# untitled.net
KiCad netlist of a schematic drawn in EAGLE
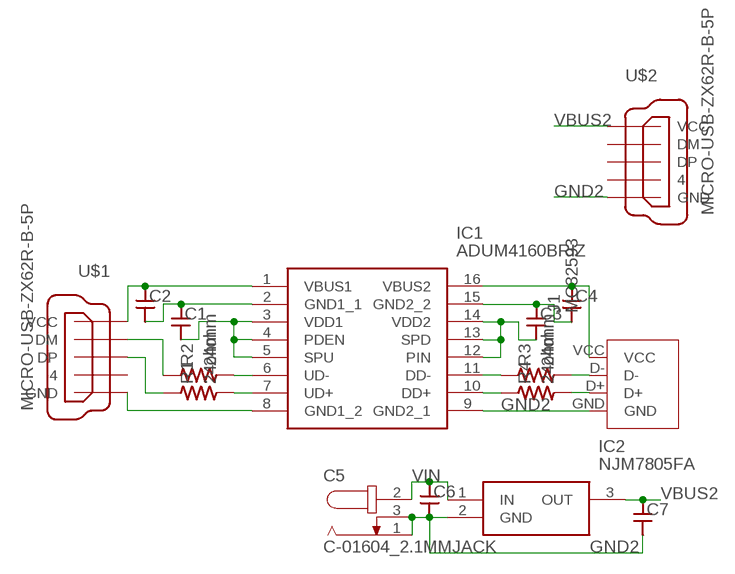
[diagram p0: schematic, sheet 1]

(export (version "E")
  (design (tool "Eeschema 10.0.6"))
  (components
    (comp (ref "C1")
      (value "CAPACITOR2012")
      (footprint "eagle-import:SMD2012")
      (libsource (lib "eagle-import") (part "CAPACITOR2012"))
    )
    (comp (ref "C2")
      (value "CAPACITOR2012")
      (footprint "eagle-import:SMD2012")
      (libsource (lib "eagle-import") (part "CAPACITOR2012"))
    )
    (comp (ref "C3")
      (value "CAPACITOR2012")
      (footprint "eagle-import:SMD2012")
      (libsource (lib "eagle-import") (part "CAPACITOR2012"))
    )
    (comp (ref "C4")
      (value "CAPACITOR2012")
      (footprint "eagle-import:SMD2012")
      (libsource (lib "eagle-import") (part "CAPACITOR2012"))
    )
    (comp (ref "C5")
      (value "C-01604_2.1MMJACK")
      (footprint "eagle-import:2.1MMJACK")
      (libsource (lib "eagle-import") (part "C-01604_2.1MMJACK"))
    )
    (comp (ref "C6")
      (value "CAPACITOR2012")
      (footprint "eagle-import:SMD2012")
      (libsource (lib "eagle-import") (part "CAPACITOR2012"))
    )
    (comp (ref "C7")
      (value "CAPACITOR2012")
      (footprint "eagle-import:SMD2012")
      (libsource (lib "eagle-import") (part "CAPACITOR2012"))
    )
    (comp (ref "IC1")
      (value "ADUM4160BRIZ")
      (footprint "eagle-import:SOIC127P1032X265-16N")
      (fields
        (field (name "MOUSER_PART_NUMBER") "584-ADUM4160BRIZ")
        (field (name "RS_PART_NUMBER") "9129894")
      )
      (libsource (lib "eagle-import") (part "ADUM4160BRIZ"))
    )
    (comp (ref "IC2")
      (value "NJM7805FA")
      (footprint "eagle-import:TO254P500X1000X2170-3P")
      (libsource (lib "eagle-import") (part "NJM7805FA"))
    )
    (comp (ref "J1")
      (value "MC32593")
      (footprint "eagle-import:MC32593")
      (libsource (lib "eagle-import") (part "MC32593"))
    )
    (comp (ref "R1")
      (value "24ohm")
      (footprint "eagle-import:SMD1608")
      (libsource (lib "eagle-import") (part "RESISTOR-US1608"))
    )
    (comp (ref "R2")
      (value "24ohm")
      (footprint "eagle-import:SMD1608")
      (libsource (lib "eagle-import") (part "RESISTOR-US1608"))
    )
    (comp (ref "R3")
      (value "24ohm")
      (footprint "eagle-import:SMD1608")
      (libsource (lib "eagle-import") (part "RESISTOR-US1608"))
    )
    (comp (ref "R4")
      (value "24ohm")
      (footprint "eagle-import:SMD1608")
      (libsource (lib "eagle-import") (part "RESISTOR-US1608"))
    )
    (comp (ref "U$1")
      (value "MICRO-USB-ZX62R-B-5P")
      (footprint "eagle-import:ZX62R-B-5P")
      (libsource (lib "eagle-import") (part "MICRO-USB-ZX62R-B-5P"))
    )
    (comp (ref "U$2")
      (value "MICRO-USB-ZX62R-B-5P")
      (footprint "eagle-import:ZX62R-B-5P")
      (libsource (lib "eagle-import") (part "MICRO-USB-ZX62R-B-5P"))
    )
  )
  (nets
    (net (code "1") (name "/GND1") (class "Default")
      (node (ref "C1") (pin "1") (pinfunction "1_1") (pintype "passive"))
      (node (ref "C2") (pin "2") (pinfunction "2_2") (pintype "passive"))
      (node (ref "IC1") (pin "2") (pinfunction "GND1_1_2") (pintype "bidirectional"))
      (node (ref "IC1") (pin "8") (pinfunction "GND1_2_8") (pintype "bidirectional"))
      (node (ref "U$1") (pin "5") (pinfunction "GND_5") (pintype "input"))
    )
    (net (code "2") (name "/GND2") (class "Default")
      (node (ref "C3") (pin "1") (pinfunction "1_1") (pintype "passive"))
      (node (ref "C4") (pin "2") (pinfunction "2_2") (pintype "passive"))
      (node (ref "C5") (pin "1") (pinfunction "GND_1") (pintype "passive"))
      (node (ref "C5") (pin "3") (pinfunction "S_3") (pintype "passive"))
      (node (ref "C6") (pin "2") (pinfunction "2_2") (pintype "passive"))
      (node (ref "C7") (pin "2") (pinfunction "2_2") (pintype "passive"))
      (node (ref "IC1") (pin "15") (pinfunction "GND2_2_15") (pintype "bidirectional"))
      (node (ref "IC1") (pin "9") (pinfunction "GND2_1_9") (pintype "bidirectional"))
      (node (ref "IC2") (pin "2") (pinfunction "GND_2") (pintype "power_in"))
      (node (ref "J1") (pin "GND") (pinfunction "GND_GND") (pintype "bidirectional"))
      (node (ref "U$2") (pin "5") (pinfunction "GND_5") (pintype "input"))
    )
    (net (code "3") (name "/VBUS2") (class "Default")
      (node (ref "C4") (pin "1") (pinfunction "1_1") (pintype "passive"))
      (node (ref "C7") (pin "1") (pinfunction "1_1") (pintype "passive"))
      (node (ref "IC1") (pin "16") (pinfunction "VBUS2_16") (pintype "bidirectional"))
      (node (ref "IC2") (pin "3") (pinfunction "OUT_3") (pintype "output"))
      (node (ref "J1") (pin "VCC") (pinfunction "VCC_VCC") (pintype "bidirectional"))
      (node (ref "U$2") (pin "1") (pinfunction "VCC_1") (pintype "input"))
    )
    (net (code "4") (name "/VIN") (class "Default")
      (node (ref "C5") (pin "2") (pinfunction "VCC_2") (pintype "passive"))
      (node (ref "C6") (pin "1") (pinfunction "1_1") (pintype "passive"))
      (node (ref "IC2") (pin "1") (pinfunction "IN_1") (pintype "input"))
    )
    (net (code "5") (name "Net-(IC1-DD+)") (class "Default")
      (node (ref "IC1") (pin "10") (pinfunction "DD+_10") (pintype "bidirectional"))
      (node (ref "R4") (pin "1") (pinfunction "1_1") (pintype "passive"))
    )
    (net (code "6") (name "Net-(IC1-DD-)") (class "Default")
      (node (ref "IC1") (pin "11") (pinfunction "DD-_11") (pintype "bidirectional"))
      (node (ref "R3") (pin "1") (pinfunction "1_1") (pintype "passive"))
    )
    (net (code "7") (name "Net-(IC1-PDEN)") (class "Default")
      (node (ref "C1") (pin "2") (pinfunction "2_2") (pintype "passive"))
      (node (ref "IC1") (pin "3") (pinfunction "VDD1_3") (pintype "bidirectional"))
      (node (ref "IC1") (pin "4") (pinfunction "PDEN_4") (pintype "bidirectional"))
      (node (ref "IC1") (pin "5") (pinfunction "SPU_5") (pintype "bidirectional"))
    )
    (net (code "8") (name "Net-(IC1-PIN)") (class "Default")
      (node (ref "C3") (pin "2") (pinfunction "2_2") (pintype "passive"))
      (node (ref "IC1") (pin "12") (pinfunction "PIN_12") (pintype "bidirectional"))
      (node (ref "IC1") (pin "13") (pinfunction "SPD_13") (pintype "bidirectional"))
      (node (ref "IC1") (pin "14") (pinfunction "VDD2_14") (pintype "bidirectional"))
    )
    (net (code "9") (name "Net-(IC1-UD+)") (class "Default")
      (node (ref "IC1") (pin "7") (pinfunction "UD+_7") (pintype "bidirectional"))
      (node (ref "R1") (pin "2") (pinfunction "2_2") (pintype "passive"))
    )
    (net (code "10") (name "Net-(IC1-UD-)") (class "Default")
      (node (ref "IC1") (pin "6") (pinfunction "UD-_6") (pintype "bidirectional"))
      (node (ref "R2") (pin "2") (pinfunction "2_2") (pintype "passive"))
    )
    (net (code "11") (name "Net-(IC1-VBUS1)") (class "Default")
      (node (ref "C2") (pin "1") (pinfunction "1_1") (pintype "passive"))
      (node (ref "IC1") (pin "1") (pinfunction "VBUS1_1") (pintype "bidirectional"))
      (node (ref "U$1") (pin "1") (pinfunction "VCC_1") (pintype "input"))
    )
    (net (code "12") (name "Net-(J1-PadD+)") (class "Default")
      (node (ref "J1") (pin "D+") (pinfunction "D+_D+") (pintype "bidirectional"))
      (node (ref "R4") (pin "2") (pinfunction "2_2") (pintype "passive"))
    )
    (net (code "13") (name "Net-(J1-PadD-)") (class "Default")
      (node (ref "J1") (pin "D-") (pinfunction "D-_D-") (pintype "bidirectional"))
      (node (ref "R3") (pin "2") (pinfunction "2_2") (pintype "passive"))
    )
    (net (code "14") (name "Net-(U$1-DM)") (class "Default")
      (node (ref "R2") (pin "1") (pinfunction "1_1") (pintype "passive"))
      (node (ref "U$1") (pin "2") (pinfunction "DM_2") (pintype "input"))
    )
    (net (code "15") (name "Net-(U$1-DP)") (class "Default")
      (node (ref "R1") (pin "1") (pinfunction "1_1") (pintype "passive"))
      (node (ref "U$1") (pin "3") (pinfunction "DP_3") (pintype "input"))
    )
    (net (code "16") (name "unconnected-(U$1-Pad4)") (class "Default")
      (node (ref "U$1") (pin "4") (pinfunction "4_4") (pintype "input"))
    )
    (net (code "17") (name "unconnected-(U$2-DM-Pad2)") (class "Default")
      (node (ref "U$2") (pin "2") (pinfunction "DM_2") (pintype "input"))
    )
    (net (code "18") (name "unconnected-(U$2-DP-Pad3)") (class "Default")
      (node (ref "U$2") (pin "3") (pinfunction "DP_3") (pintype "input"))
    )
    (net (code "19") (name "unconnected-(U$2-Pad4)") (class "Default")
      (node (ref "U$2") (pin "4") (pinfunction "4_4") (pintype "input"))
    )
  )
)
